# Shematic.net
KiCad netlist of a schematic drawn in Altium Designer
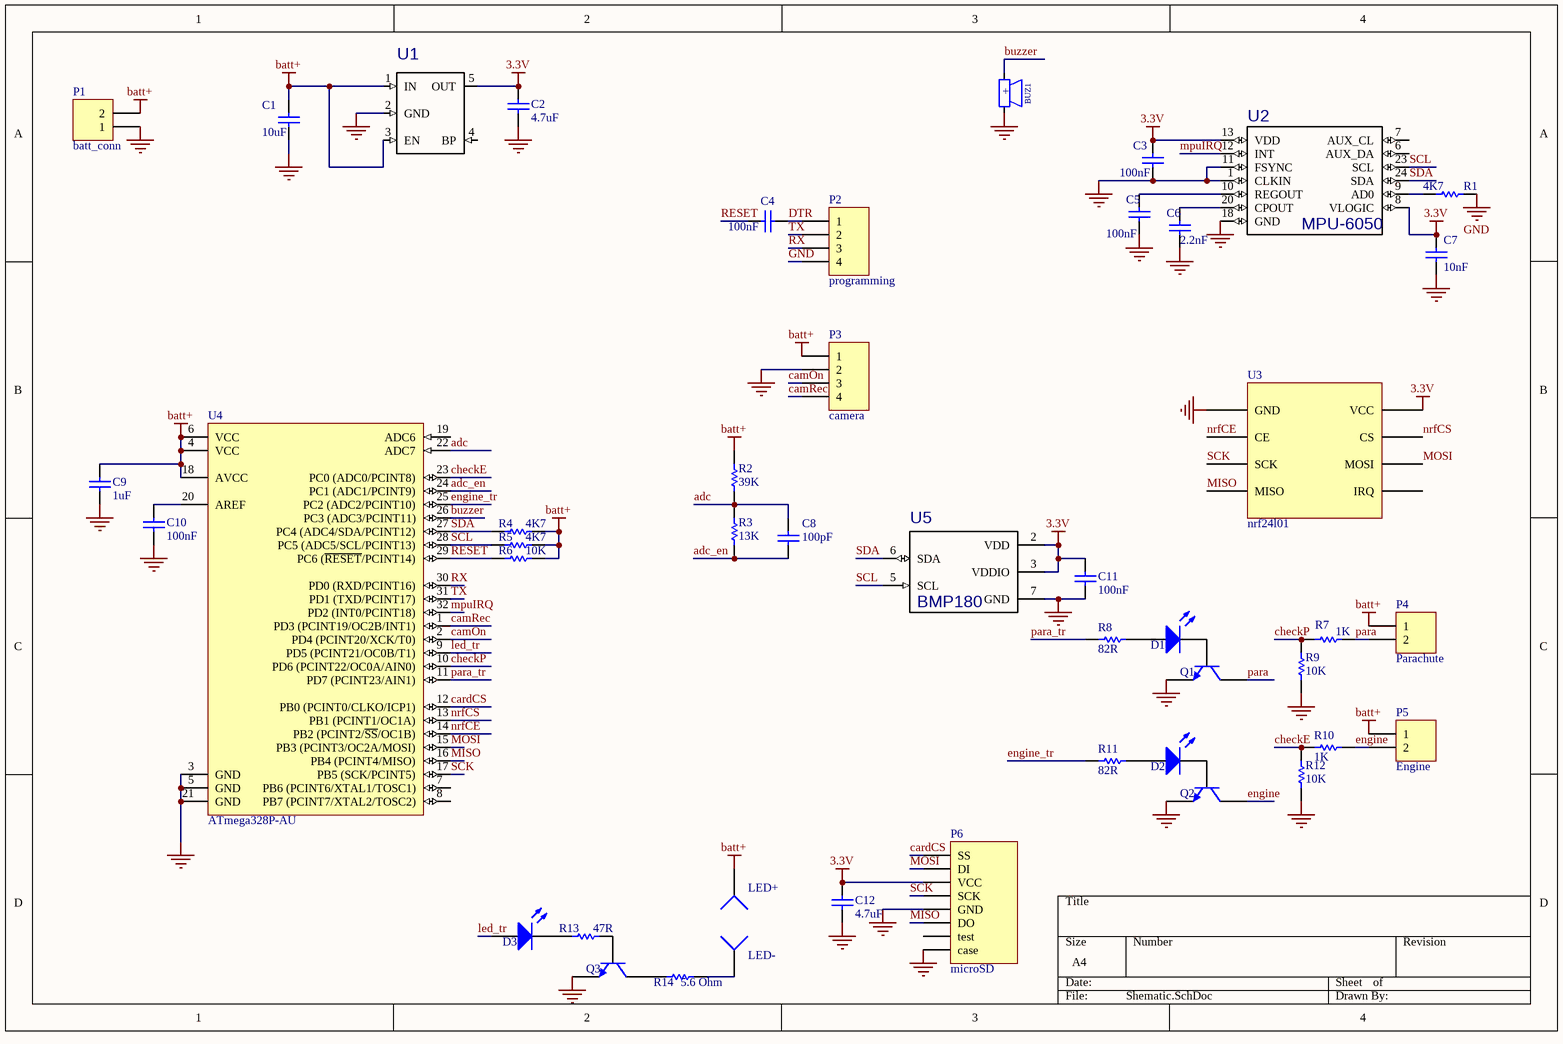
[diagram p0: Shematic.SchDoc]

(export (version "E")
  (design (tool "Eeschema 10.0.6"))
  (components
    (comp (ref "BUZ1")
      (value "Buzzer")
      (footprint "BUZ12X7,6MM")
      (description "BUZ12X7,6MM")
      (libsource (lib "Library") (part "Buzzer"))
    )
    (comp (ref "C1")
      (value "10uF")
      (footprint "CAPC1206(3216)190_N")
      (description "CAP 10uF 50V ±20% 1206 (3216 Metric) Thickness 1.9mm SMD")
      (fields (field (name "TOLERANCE") "Â±20%"))
      (libsource (lib "Altium Content Vault") (part "CMP-1037-04983-1"))
    )
    (comp (ref "C2")
      (value "4.7uF")
      (footprint "CAPC0603(1608)100_N")
      (description "CAP 4.7uF 16V ±20% 0603 (1608 Metric) Thickness 1mm SMD")
      (fields (field (name "TOLERANCE") "Â±20%"))
      (libsource (lib "Altium Content Vault") (part "CMP-1035-02789-1"))
    )
    (comp (ref "C3")
      (value "100nF")
      (footprint "CAPC0603(1608)100_N")
      (description "CAP 100nF 16V ±20% 0603 (1608 Metric) Thickness 1mm SMD")
      (fields (field (name "TOLERANCE") "Â±20%"))
      (libsource (lib "Altium Content Vault") (part "CMP-1035-02585-1"))
    )
    (comp (ref "C4")
      (value "100nF")
      (footprint "CAPC0603(1608)100_N")
      (description "CAP 100nF 16V ±20% 0603 (1608 Metric) Thickness 1mm SMD")
      (fields (field (name "TOLERANCE") "Â±20%"))
      (libsource (lib "Altium Content Vault") (part "CMP-1035-02585-1"))
    )
    (comp (ref "C5")
      (value "100nF")
      (footprint "CAPC0603(1608)100_N")
      (description "CAP 100nF 16V ±20% 0603 (1608 Metric) Thickness 1mm SMD")
      (fields (field (name "TOLERANCE") "Â±20%"))
      (libsource (lib "Altium Content Vault") (part "CMP-1035-02585-1"))
    )
    (comp (ref "C6")
      (value "2.2nF")
      (footprint "CAPC0603(1608)100_L")
      (description "CAP 2.2nF 16V ±20% 0603 (1608 Metric) Thickness 1mm SMD")
      (fields (field (name "TOLERANCE") "Â±20%"))
      (libsource (lib "Altium Content Vault") (part "CMP-1035-02030-1"))
    )
    (comp (ref "C7")
      (value "10nF")
      (footprint "CAPC0603(1608)100_L")
      (description "CAP 10nF 16V ±20% 0603 (1608 Metric) Thickness 1mm SMD")
      (fields (field (name "TOLERANCE") "Â±20%"))
      (libsource (lib "Altium Content Vault") (part "CMP-1035-02312-1"))
    )
    (comp (ref "C8")
      (value "100pF")
      (footprint "CAPC0805(2012)100_L")
      (description "CAP 200pF 16V ±10% 0805 (2012 Metric) Thickness 1mm SMD")
      (fields (field (name "TOLERANCE") "Â±10%"))
      (libsource (lib "Altium Content Vault") (part "CMP-1036-02260-1"))
    )
    (comp (ref "C9")
      (value "1uF")
      (footprint "CAPC0603(1608)100_L")
      (description "CAP 1uF 16V ±20% 0603 (1608 Metric) Thickness 1mm SMD")
      (fields (field (name "TOLERANCE") "Â±20%"))
      (libsource (lib "Altium Content Vault") (part "CMP-1035-02738-1"))
    )
    (comp (ref "C10")
      (value "100nF")
      (footprint "CAPC0603(1608)100_N")
      (description "CAP 100nF 16V ±20% 0603 (1608 Metric) Thickness 1mm SMD")
      (fields (field (name "TOLERANCE") "Â±20%"))
      (libsource (lib "Altium Content Vault") (part "CMP-1035-02585-1"))
    )
    (comp (ref "C11")
      (value "100nF")
      (footprint "CAPC0603(1608)100_N")
      (description "CAP 100nF 16V ±20% 0603 (1608 Metric) Thickness 1mm SMD")
      (fields (field (name "TOLERANCE") "Â±20%"))
      (libsource (lib "Altium Content Vault") (part "CMP-1035-02585-1"))
    )
    (comp (ref "C12")
      (value "4.7uF")
      (footprint "CAPC0603(1608)100_N")
      (description "CAP 4.7uF 16V ±20% 0603 (1608 Metric) Thickness 1mm SMD")
      (fields (field (name "TOLERANCE") "Â±20%"))
      (libsource (lib "Altium Content Vault") (part "CMP-1035-02789-1"))
    )
    (comp (ref "D1")
      (value "LED0")
      (footprint "LED0805")
      (description "Typical INFRARED GaAs LED")
      (fields (field (name "PUBLISHER") "Altium Limited"))
      (libsource (lib "Library") (part "LED0"))
    )
    (comp (ref "D2")
      (value "LED0")
      (footprint "LED0805")
      (description "Typical INFRARED GaAs LED")
      (fields (field (name "PUBLISHER") "Altium Limited"))
      (libsource (lib "Library") (part "LED0"))
    )
    (comp (ref "D3")
      (value "LED0")
      (footprint "LED0805")
      (description "Typical INFRARED GaAs LED")
      (fields (field (name "PUBLISHER") "Altium Limited"))
      (libsource (lib "Library") (part "LED0"))
    )
    (comp (ref "J1")
      (value "LED+")
      (footprint "PIN1")
      (description "Socket")
      (fields (field (name "PUBLISHER") "Altium Limited"))
      (libsource (lib "Miscellaneous Connectors") (part "Socket"))
    )
    (comp (ref "J2")
      (value "LED-")
      (footprint "PIN1")
      (description "Socket")
      (fields (field (name "PUBLISHER") "Altium Limited"))
      (libsource (lib "Miscellaneous Connectors") (part "Socket"))
    )
    (comp (ref "P1")
      (value "batt_conn")
      (footprint "Library_pcb:XH-2")
      (description "XH 2-pin, 2.4mm pitch")
      (fields (field (name "PUBLISHER") "Altium Limited"))
      (libsource (lib "Library") (part "XH-2"))
    )
    (comp (ref "P2")
      (value "programming")
      (footprint "HDR1X4")
      (description "Header, 4-Pin")
      (fields (field (name "PUBLISHER") "Altium Limited"))
      (libsource (lib "Miscellaneous Connectors") (part "Header 4"))
    )
    (comp (ref "P3")
      (value "camera")
      (footprint "Library_pcb:XH-4")
      (description "XH 4-pin, 2.4mm pitch")
      (fields (field (name "PUBLISHER") "Altium Limited"))
      (libsource (lib "Library") (part "XH-4"))
    )
    (comp (ref "P4")
      (value "Parachute")
      (footprint "Library_pcb:screw-con-2")
      (description "screw con 2-pin, 5.08mm pitch")
      (fields (field (name "PUBLISHER") "Altium Limited"))
      (libsource (lib "") (part "screw-con-2_1"))
    )
    (comp (ref "P5")
      (value "Engine")
      (footprint "Library_pcb:screw-con-2")
      (description "screw con 2-pin, 5.08mm pitch")
      (fields (field (name "PUBLISHER") "Altium Limited"))
      (libsource (lib "Library") (part "screw-con-2"))
    )
    (comp (ref "P6")
      (value "microSD")
      (footprint "Library_pcb:Micro SD holder")
      (description "microSD holder")
      (fields (field (name "PUBLISHER") "Altium Limited"))
      (libsource (lib "Library") (part "microSD"))
    )
    (comp (ref "Q1")
      (value "MMBT2222A")
      (footprint "INF-SOT23_L")
      (description "NPN Silicon Switching Transistor, 40 V VCEO, 600 mA IC, SOT23, Reel, Green")
      (fields (field (name "MANUFACTURER") "Infineon"))
      (libsource (lib "Altium Content Vault") (part "CMP-1178-00009-1"))
    )
    (comp (ref "Q2")
      (value "MMBT2222A")
      (footprint "INF-SOT23_N")
      (description "NPN Silicon Switching Transistor, 40 V VCEO, 600 mA IC, SOT23, Reel, Green")
      (fields (field (name "MANUFACTURER") "Infineon"))
      (libsource (lib "Altium Content Vault") (part "CMP-1178-00009-1"))
    )
    (comp (ref "Q3")
      (value "MMBT2222A")
      (footprint "INF-SOT23_M")
      (description "NPN Silicon Switching Transistor, 40 V VCEO, 600 mA IC, SOT23, Reel, Green")
      (fields (field (name "MANUFACTURER") "Infineon"))
      (libsource (lib "Altium Content Vault") (part "CMP-1178-00009-1"))
    )
    (comp (ref "R1")
      (value "4K7")
      (footprint "RESC0603(1608)_N")
      (description "4K7 0.1W 5% 0603 (1608 Metric)  SMD")
      (fields (field (name "TOLERANCE") "5 %") (field (name "POWER") "0.1 W"))
      (libsource (lib "Altium Content Vault") (part "CMP-1012-00090-1"))
    )
    (comp (ref "R2")
      (value "39K")
      (footprint "Miscellaneous Devices:6-0805_L")
      (description "39K 0.25W 5% 1206 (3216 Metric)  SMD")
      (fields (field (name "TOLERANCE") "5 %") (field (name "POWER") "0.25 W"))
      (libsource (lib "altium-import") (part "root_1_CMP-1014-00112-1_"))
    )
    (comp (ref "R3")
      (value "13K")
      (footprint "RESC0805(2012)_L")
      (description "13K 0.125W 5% 0805 (2012 Metric)  SMD")
      (fields (field (name "POWER") "0.125 W") (field (name "TOLERANCE") "5 %"))
      (libsource (lib "Altium Content Vault") (part "CMP-1013-00101-1"))
    )
    (comp (ref "R4")
      (value "4K7")
      (footprint "RESC0603(1608)_N")
      (description "4K7 0.1W 5% 0603 (1608 Metric)  SMD")
      (fields (field (name "TOLERANCE") "5 %") (field (name "POWER") "0.1 W"))
      (libsource (lib "Altium Content Vault") (part "CMP-1012-00090-1"))
    )
    (comp (ref "R5")
      (value "4K7")
      (footprint "RESC0603(1608)_N")
      (description "4K7 0.1W 5% 0603 (1608 Metric)  SMD")
      (fields (field (name "TOLERANCE") "5 %") (field (name "POWER") "0.1 W"))
      (libsource (lib "Altium Content Vault") (part "CMP-1012-00090-1"))
    )
    (comp (ref "R6")
      (value "10K")
      (footprint "Miscellaneous Devices:6-0805_L")
      (fields (field (name "POWER") "0.25 W") (field (name "TOLERANCE") "5 %"))
      (libsource (lib "altium-import") (part "root_0_CMP-1014-00098-1_"))
    )
    (comp (ref "R7")
      (value "1K")
      (footprint "RESC0805(2012)_N")
      (description "1K 0.125W 5% 0805 (2012 Metric)  SMD")
      (fields (field (name "POWER") "0.125 W") (field (name "TOLERANCE") "5 %"))
      (libsource (lib "Altium Content Vault") (part "CMP-1013-00074-1"))
    )
    (comp (ref "R8")
      (value "82R")
      (footprint "RESC0805(2012)_L")
      (description "2R4 0.125W 5% 0805 (2012 Metric)  SMD")
      (fields (field (name "POWER") "0.125 W") (field (name "TOLERANCE") "5 %"))
      (libsource (lib "Altium Content Vault") (part "CMP-1013-00011-1"))
    )
    (comp (ref "R9")
      (value "10K")
      (footprint "RESC0805(2012)_L")
      (description "10K 0.125W 5% 0805 (2012 Metric)  SMD")
      (fields (field (name "POWER") "0.125 W") (field (name "TOLERANCE") "5 %"))
      (libsource (lib "Altium Content Vault") (part "CMP-1013-00098-1"))
    )
    (comp (ref "R10")
      (value "1K")
      (footprint "RESC1206(3216)_N")
      (description "1K 0.25W 5% 1206 (3216 Metric)  SMD")
      (fields (field (name "TOLERANCE") "5 %") (field (name "POWER") "0.25 W"))
      (libsource (lib "Altium Content Vault") (part "CMP-1014-00074-1"))
    )
    (comp (ref "R11")
      (value "82R")
      (footprint "RESC0805(2012)_L")
      (description "2R4 0.125W 5% 0805 (2012 Metric)  SMD")
      (fields (field (name "POWER") "0.125 W") (field (name "TOLERANCE") "5 %"))
      (libsource (lib "Altium Content Vault") (part "CMP-1013-00011-1"))
    )
    (comp (ref "R12")
      (value "10K")
      (footprint "RESC0805(2012)_L")
      (description "10K 0.125W 5% 0805 (2012 Metric)  SMD")
      (fields (field (name "POWER") "0.125 W") (field (name "TOLERANCE") "5 %"))
      (libsource (lib "Altium Content Vault") (part "CMP-1013-00098-1"))
    )
    (comp (ref "R13")
      (value "47R")
      (footprint "RESC0805(2012)_N")
      (description "270R 0.125W 5% 0805 (2012 Metric)  SMD")
      (fields (field (name "POWER") "0.125 W") (field (name "TOLERANCE") "5 %"))
      (libsource (lib "Altium Content Vault") (part "CMP-1013-00060-1"))
    )
    (comp (ref "R14")
      (value "5.6 Ohm")
      (footprint "RESC0805(2012)_M")
      (description "100R 0.125W 5% 0805 (2012 Metric)  SMD")
      (fields (field (name "TOLERANCE") "5 %") (field (name "POWER") "0.125 W"))
      (libsource (lib "Altium Content Vault") (part "CMP-1013-00050-1"))
    )
    (comp (ref "U1")
      (value "MIC5205")
      (footprint "SOT23-5L_M")
      (description "LDO (KB33)")
      (libsource (lib "Library") (part "MIC5205"))
    )
    (comp (ref "U2")
      (value "MPU-6050")
      (footprint "QFN-24-4MM2")
      (libsource (lib "Library") (part "MPU-6050"))
    )
    (comp (ref "U3")
      (value "nrf24l01")
      (footprint "NRF24l01 ant")
      (description "Wirless module 2.4GHz")
      (libsource (lib "Library") (part "NRF24L01"))
    )
    (comp (ref "U4")
      (value "ATmega328P-AU")
      (footprint "32A_M")
      (libsource (lib "Altium Content Vault") (part "MC-8B-ATM48-SQ32"))
    )
    (comp (ref "U5")
      (value "BMP180")
      (footprint "Library_pcb:BMP180")
      (libsource (lib "Library") (part "BMP180"))
    )
  )
  (nets
    (net (code "1") (name "/DTR") (class "Default")
      (node (ref "C4") (pin "2") (pinfunction "2_2") (pintype "passive"))
      (node (ref "P2") (pin "1") (pinfunction "1_1") (pintype "passive"))
    )
    (net (code "2") (name "/MISO") (class "Default")
      (node (ref "P6") (pin "7") (pinfunction "DO_7") (pintype "passive"))
      (node (ref "U3") (pin "7") (pinfunction "MISO_7") (pintype "passive"))
      (node (ref "U4") (pin "16") (pinfunction "PB4_(PCINT4/MISO)_16") (pintype "bidirectional"))
    )
    (net (code "3") (name "/MOSI") (class "Default")
      (node (ref "P6") (pin "3") (pinfunction "DI_3") (pintype "passive"))
      (node (ref "U3") (pin "6") (pinfunction "MOSI_6") (pintype "passive"))
      (node (ref "U4") (pin "15") (pinfunction "PB3_(PCINT3/OC2A/MOSI)_15") (pintype "bidirectional"))
    )
    (net (code "4") (name "/RESET") (class "Default")
      (node (ref "C4") (pin "1") (pinfunction "1_1") (pintype "passive"))
      (node (ref "R6") (pin "1") (pinfunction "1_1") (pintype "passive"))
      (node (ref "U4") (pin "29") (pinfunction "PC6_(~{RESET}/PCINT14)_29") (pintype "bidirectional"))
    )
    (net (code "5") (name "/RX") (class "Default")
      (node (ref "P2") (pin "3") (pinfunction "3_3") (pintype "passive"))
      (node (ref "U4") (pin "30") (pinfunction "PD0_(RXD/PCINT16)_30") (pintype "bidirectional"))
    )
    (net (code "6") (name "/SCK") (class "Default")
      (node (ref "P6") (pin "5") (pinfunction "SCK_5") (pintype "passive"))
      (node (ref "U3") (pin "5") (pinfunction "SCK_5") (pintype "passive"))
      (node (ref "U4") (pin "17") (pinfunction "PB5_(SCK/PCINT5)_17") (pintype "bidirectional"))
    )
    (net (code "7") (name "/SCL") (class "Default")
      (node (ref "R5") (pin "1") (pinfunction "1_1") (pintype "passive"))
      (node (ref "U2") (pin "23") (pinfunction "SCL_23") (pintype "bidirectional"))
      (node (ref "U4") (pin "28") (pinfunction "PC5_(ADC5/SCL/PCINT13)_28") (pintype "bidirectional"))
      (node (ref "U5") (pin "5") (pinfunction "SCL_5") (pintype "input"))
    )
    (net (code "8") (name "/SDA") (class "Default")
      (node (ref "R4") (pin "1") (pinfunction "1_1") (pintype "passive"))
      (node (ref "U2") (pin "24") (pinfunction "SDA_24") (pintype "bidirectional"))
      (node (ref "U4") (pin "27") (pinfunction "PC4_(ADC4/SDA/PCINT12)_27") (pintype "bidirectional"))
      (node (ref "U5") (pin "6") (pinfunction "SDA_6") (pintype "bidirectional"))
    )
    (net (code "9") (name "/TX") (class "Default")
      (node (ref "P2") (pin "2") (pinfunction "2_2") (pintype "passive"))
      (node (ref "U4") (pin "31") (pinfunction "PD1_(TXD/PCINT17)_31") (pintype "bidirectional"))
    )
    (net (code "10") (name "/adc") (class "Default")
      (node (ref "C8") (pin "2") (pinfunction "2_2") (pintype "passive"))
      (node (ref "R2") (pin "1") (pinfunction "1_1") (pintype "passive"))
      (node (ref "R3") (pin "1") (pinfunction "1_1") (pintype "passive"))
      (node (ref "U4") (pin "22") (pinfunction "ADC7_22") (pintype "input"))
    )
    (net (code "11") (name "/adc_en") (class "Default")
      (node (ref "C8") (pin "1") (pinfunction "1_1") (pintype "passive"))
      (node (ref "R3") (pin "2") (pinfunction "2_2") (pintype "passive"))
      (node (ref "U4") (pin "24") (pinfunction "PC1_(ADC1/PCINT9)_24") (pintype "bidirectional"))
    )
    (net (code "12") (name "/buzzer") (class "Default")
      (node (ref "BUZ1") (pin "2") (pinfunction "2_2") (pintype "passive"))
      (node (ref "U4") (pin "26") (pinfunction "PC3_(ADC3/PCINT11)_26") (pintype "bidirectional"))
    )
    (net (code "13") (name "/camOn") (class "Default")
      (node (ref "P3") (pin "3") (pinfunction "3_3") (pintype "passive"))
      (node (ref "U4") (pin "2") (pinfunction "PD4_(PCINT20/XCK/T0)_2") (pintype "bidirectional"))
    )
    (net (code "14") (name "/camRec") (class "Default")
      (node (ref "P3") (pin "4") (pinfunction "4_4") (pintype "passive"))
      (node (ref "U4") (pin "1") (pinfunction "PD3_(PCINT19/OC2B/INT1)_1") (pintype "bidirectional"))
    )
    (net (code "15") (name "/cardCS") (class "Default")
      (node (ref "P6") (pin "2") (pinfunction "SS_2") (pintype "passive"))
      (node (ref "U4") (pin "12") (pinfunction "PB0_(PCINT0/CLKO/ICP1)_12") (pintype "bidirectional"))
    )
    (net (code "16") (name "/checkE") (class "Default")
      (node (ref "R10") (pin "1") (pinfunction "1_1") (pintype "passive"))
      (node (ref "R12") (pin "2") (pinfunction "2_2") (pintype "passive"))
      (node (ref "U4") (pin "23") (pinfunction "PC0_(ADC0/PCINT8)_23") (pintype "bidirectional"))
    )
    (net (code "17") (name "/checkP") (class "Default")
      (node (ref "R7") (pin "1") (pinfunction "1_1") (pintype "passive"))
      (node (ref "R9") (pin "2") (pinfunction "2_2") (pintype "passive"))
      (node (ref "U4") (pin "10") (pinfunction "PD6_(PCINT22/OC0A/AIN0)_10") (pintype "bidirectional"))
    )
    (net (code "18") (name "/engine") (class "Default")
      (node (ref "P5") (pin "2") (pinfunction "2_2") (pintype "passive"))
      (node (ref "Q2") (pin "3") (pinfunction "C_3") (pintype "passive"))
      (node (ref "R10") (pin "2") (pinfunction "2_2") (pintype "passive"))
    )
    (net (code "19") (name "/engine_tr") (class "Default")
      (node (ref "R11") (pin "1") (pinfunction "1_1") (pintype "passive"))
      (node (ref "U4") (pin "25") (pinfunction "PC2_(ADC2/PCINT10)_25") (pintype "bidirectional"))
    )
    (net (code "20") (name "/led_tr") (class "Default")
      (node (ref "D3") (pin "1") (pinfunction "A_1") (pintype "passive"))
      (node (ref "U4") (pin "9") (pinfunction "PD5_(PCINT21/OC0B/T1)_9") (pintype "bidirectional"))
    )
    (net (code "21") (name "/mpuIRQ") (class "Default")
      (node (ref "U2") (pin "12") (pinfunction "INT_12") (pintype "bidirectional"))
      (node (ref "U4") (pin "32") (pinfunction "PD2_(INT0/PCINT18)_32") (pintype "bidirectional"))
    )
    (net (code "22") (name "/nrfCE") (class "Default")
      (node (ref "U3") (pin "3") (pinfunction "CE_3") (pintype "passive"))
      (node (ref "U4") (pin "14") (pinfunction "PB2_(PCINT2/~{SS}/OC1B)_14") (pintype "bidirectional"))
    )
    (net (code "23") (name "/nrfCS") (class "Default")
      (node (ref "U3") (pin "4") (pinfunction "CS_4") (pintype "passive"))
      (node (ref "U4") (pin "13") (pinfunction "PB1_(PCINT1/OC1A)_13") (pintype "bidirectional"))
    )
    (net (code "24") (name "/para") (class "Default")
      (node (ref "P4") (pin "1") (pinfunction "2_1") (pintype "passive"))
      (node (ref "Q1") (pin "3") (pinfunction "C_3") (pintype "passive"))
      (node (ref "R7") (pin "2") (pinfunction "2_2") (pintype "passive"))
    )
    (net (code "25") (name "/para_tr") (class "Default")
      (node (ref "R8") (pin "1") (pinfunction "1_1") (pintype "passive"))
      (node (ref "U4") (pin "11") (pinfunction "PD7_(PCINT23/AIN1)_11") (pintype "bidirectional"))
    )
    (net (code "26") (name "3.3V") (class "Default")
      (node (ref "C11") (pin "2") (pinfunction "2_2") (pintype "passive"))
      (node (ref "C12") (pin "2") (pinfunction "2_2") (pintype "passive"))
      (node (ref "C2") (pin "2") (pinfunction "2_2") (pintype "passive"))
      (node (ref "C3") (pin "1") (pinfunction "1_1") (pintype "passive"))
      (node (ref "C7") (pin "2") (pinfunction "2_2") (pintype "passive"))
      (node (ref "P6") (pin "4") (pinfunction "VCC_4") (pintype "passive"))
      (node (ref "U1") (pin "5") (pinfunction "OUT_5") (pintype "passive"))
      (node (ref "U2") (pin "13") (pinfunction "VDD_13") (pintype "bidirectional"))
      (node (ref "U2") (pin "8") (pinfunction "VLOGIC_8") (pintype "bidirectional"))
      (node (ref "U3") (pin "2") (pinfunction "VCC_2") (pintype "passive"))
      (node (ref "U5") (pin "2") (pinfunction "VDD_2") (pintype "power_in"))
      (node (ref "U5") (pin "3") (pinfunction "VDDIO_3") (pintype "power_in"))
    )
    (net (code "27") (name "GND") (class "Default")
      (node (ref "BUZ1") (pin "1") (pinfunction "1_1") (pintype "passive"))
      (node (ref "C1") (pin "1") (pinfunction "1_1") (pintype "passive"))
      (node (ref "C10") (pin "1") (pinfunction "1_1") (pintype "passive"))
      (node (ref "C11") (pin "1") (pinfunction "1_1") (pintype "passive"))
      (node (ref "C12") (pin "1") (pinfunction "1_1") (pintype "passive"))
      (node (ref "C2") (pin "1") (pinfunction "1_1") (pintype "passive"))
      (node (ref "C3") (pin "2") (pinfunction "2_2") (pintype "passive"))
      (node (ref "C5") (pin "1") (pinfunction "1_1") (pintype "passive"))
      (node (ref "C6") (pin "1") (pinfunction "1_1") (pintype "passive"))
      (node (ref "C7") (pin "1") (pinfunction "1_1") (pintype "passive"))
      (node (ref "C9") (pin "1") (pinfunction "1_1") (pintype "passive"))
      (node (ref "P1") (pin "1") (pinfunction "1_1") (pintype "passive"))
      (node (ref "P2") (pin "4") (pinfunction "4_4") (pintype "passive"))
      (node (ref "P3") (pin "2") (pinfunction "2_2") (pintype "passive"))
      (node (ref "P6") (pin "0") (pinfunction "case_0") (pintype "passive"))
      (node (ref "P6") (pin "6") (pinfunction "GND_6") (pintype "passive"))
      (node (ref "Q1") (pin "2") (pinfunction "E_2") (pintype "passive"))
      (node (ref "Q2") (pin "2") (pinfunction "E_2") (pintype "passive"))
      (node (ref "Q3") (pin "2") (pinfunction "E_2") (pintype "passive"))
      (node (ref "R1") (pin "2") (pinfunction "2_2") (pintype "passive"))
      (node (ref "R12") (pin "1") (pinfunction "1_1") (pintype "passive"))
      (node (ref "R9") (pin "1") (pinfunction "1_1") (pintype "passive"))
      (node (ref "U1") (pin "2") (pinfunction "GND_2") (pintype "input"))
      (node (ref "U2") (pin "1") (pinfunction "CLKIN_1") (pintype "bidirectional"))
      (node (ref "U2") (pin "11") (pinfunction "FSYNC_11") (pintype "bidirectional"))
      (node (ref "U2") (pin "18") (pinfunction "GND_18") (pintype "bidirectional"))
      (node (ref "U3") (pin "1") (pinfunction "GND_1") (pintype "passive"))
      (node (ref "U4") (pin "21") (pinfunction "GND_21") (pintype "power_in"))
      (node (ref "U4") (pin "3") (pinfunction "GND_3") (pintype "power_in"))
      (node (ref "U4") (pin "5") (pinfunction "GND_5") (pintype "power_in"))
      (node (ref "U5") (pin "7") (pinfunction "GND_7") (pintype "power_in"))
    )
    (net (code "28") (name "Net-(D1-A)") (class "Default")
      (node (ref "D1") (pin "1") (pinfunction "A_1") (pintype "passive"))
      (node (ref "R8") (pin "2") (pinfunction "2_2") (pintype "passive"))
    )
    (net (code "29") (name "Net-(D1-K)") (class "Default")
      (node (ref "D1") (pin "2") (pinfunction "K_2") (pintype "passive"))
      (node (ref "Q1") (pin "1") (pinfunction "B_1") (pintype "passive"))
    )
    (net (code "30") (name "Net-(D2-A)") (class "Default")
      (node (ref "D2") (pin "1") (pinfunction "A_1") (pintype "passive"))
      (node (ref "R11") (pin "2") (pinfunction "2_2") (pintype "passive"))
    )
    (net (code "31") (name "Net-(D2-K)") (class "Default")
      (node (ref "D2") (pin "2") (pinfunction "K_2") (pintype "passive"))
      (node (ref "Q2") (pin "1") (pinfunction "B_1") (pintype "passive"))
    )
    (net (code "32") (name "Net-(D3-K)") (class "Default")
      (node (ref "D3") (pin "2") (pinfunction "K_2") (pintype "passive"))
      (node (ref "R13") (pin "1") (pinfunction "1_1") (pintype "passive"))
    )
    (net (code "33") (name "Net-(J2-Pad1)") (class "Default")
      (node (ref "J2") (pin "1") (pinfunction "1_1") (pintype "passive"))
      (node (ref "R14") (pin "2") (pinfunction "2_2") (pintype "passive"))
    )
    (net (code "34") (name "Net-(Q3-B)") (class "Default")
      (node (ref "Q3") (pin "1") (pinfunction "B_1") (pintype "passive"))
      (node (ref "R13") (pin "2") (pinfunction "2_2") (pintype "passive"))
    )
    (net (code "35") (name "Net-(Q3-C)") (class "Default")
      (node (ref "Q3") (pin "3") (pinfunction "C_3") (pintype "passive"))
      (node (ref "R14") (pin "1") (pinfunction "1_1") (pintype "passive"))
    )
    (net (code "36") (name "Net-(U2-AD0)") (class "Default")
      (node (ref "R1") (pin "1") (pinfunction "1_1") (pintype "passive"))
      (node (ref "U2") (pin "9") (pinfunction "AD0_9") (pintype "bidirectional"))
    )
    (net (code "37") (name "Net-(U2-CPOUT)") (class "Default")
      (node (ref "C6") (pin "2") (pinfunction "2_2") (pintype "passive"))
      (node (ref "U2") (pin "20") (pinfunction "CPOUT_20") (pintype "bidirectional"))
    )
    (net (code "38") (name "Net-(U2-REGOUT)") (class "Default")
      (node (ref "C5") (pin "2") (pinfunction "2_2") (pintype "passive"))
      (node (ref "U2") (pin "10") (pinfunction "REGOUT_10") (pintype "bidirectional"))
    )
    (net (code "39") (name "Net-(U4-AREF)") (class "Default")
      (node (ref "C10") (pin "2") (pinfunction "2_2") (pintype "passive"))
      (node (ref "U4") (pin "20") (pinfunction "AREF_20") (pintype "passive"))
    )
    (net (code "40") (name "batt+") (class "Default")
      (node (ref "C1") (pin "2") (pinfunction "2_2") (pintype "passive"))
      (node (ref "C9") (pin "2") (pinfunction "2_2") (pintype "passive"))
      (node (ref "J1") (pin "1") (pinfunction "1_1") (pintype "passive"))
      (node (ref "P1") (pin "2") (pinfunction "2_2") (pintype "passive"))
      (node (ref "P3") (pin "1") (pinfunction "1_1") (pintype "passive"))
      (node (ref "P4") (pin "2") (pinfunction "1_2") (pintype "passive"))
      (node (ref "P5") (pin "1") (pinfunction "1_1") (pintype "passive"))
      (node (ref "R2") (pin "2") (pinfunction "2_2") (pintype "passive"))
      (node (ref "R4") (pin "2") (pinfunction "2_2") (pintype "passive"))
      (node (ref "R5") (pin "2") (pinfunction "2_2") (pintype "passive"))
      (node (ref "R6") (pin "2") (pinfunction "2_2") (pintype "passive"))
      (node (ref "U1") (pin "1") (pinfunction "IN_1") (pintype "input"))
      (node (ref "U1") (pin "3") (pinfunction "EN_3") (pintype "input"))
      (node (ref "U4") (pin "18") (pinfunction "AVCC_18") (pintype "power_in"))
      (node (ref "U4") (pin "4") (pinfunction "VCC_4") (pintype "power_in"))
      (node (ref "U4") (pin "6") (pinfunction "VCC_6") (pintype "power_in"))
    )
    (net (code "41") (name "unconnected-(P6-test-Pad9)") (class "Default")
      (node (ref "P6") (pin "9") (pinfunction "test_9") (pintype "passive"))
    )
    (net (code "42") (name "unconnected-(U1-BP-Pad4)") (class "Default")
      (node (ref "U1") (pin "4") (pinfunction "BP_4") (pintype "input"))
    )
    (net (code "43") (name "unconnected-(U2-AUX_CL-Pad7)") (class "Default")
      (node (ref "U2") (pin "7") (pinfunction "AUX_CL_7") (pintype "bidirectional"))
    )
    (net (code "44") (name "unconnected-(U2-AUX_DA-Pad6)") (class "Default")
      (node (ref "U2") (pin "6") (pinfunction "AUX_DA_6") (pintype "bidirectional"))
    )
    (net (code "45") (name "unconnected-(U3-IRQ-Pad8)") (class "Default")
      (node (ref "U3") (pin "8") (pinfunction "IRQ_8") (pintype "passive"))
    )
    (net (code "46") (name "unconnected-(U4-ADC6-Pad19)") (class "Default")
      (node (ref "U4") (pin "19") (pinfunction "ADC6_19") (pintype "input"))
    )
    (net (code "47") (name "unconnected-(U4-PB6_(PCINT6{slash}XTAL1{slash}TOSC1)-Pad7)") (class "Default")
      (node (ref "U4") (pin "7") (pinfunction "PB6_(PCINT6/XTAL1/TOSC1)_7") (pintype "bidirectional"))
    )
    (net (code "48") (name "unconnected-(U4-PB7_(PCINT7{slash}XTAL2{slash}TOSC2)-Pad8)") (class "Default")
      (node (ref "U4") (pin "8") (pinfunction "PB7_(PCINT7/XTAL2/TOSC2)_8") (pintype "bidirectional"))
    )
  )
)
